# 02_MCU.net
KiCad netlist of a schematic drawn in Altium Designer
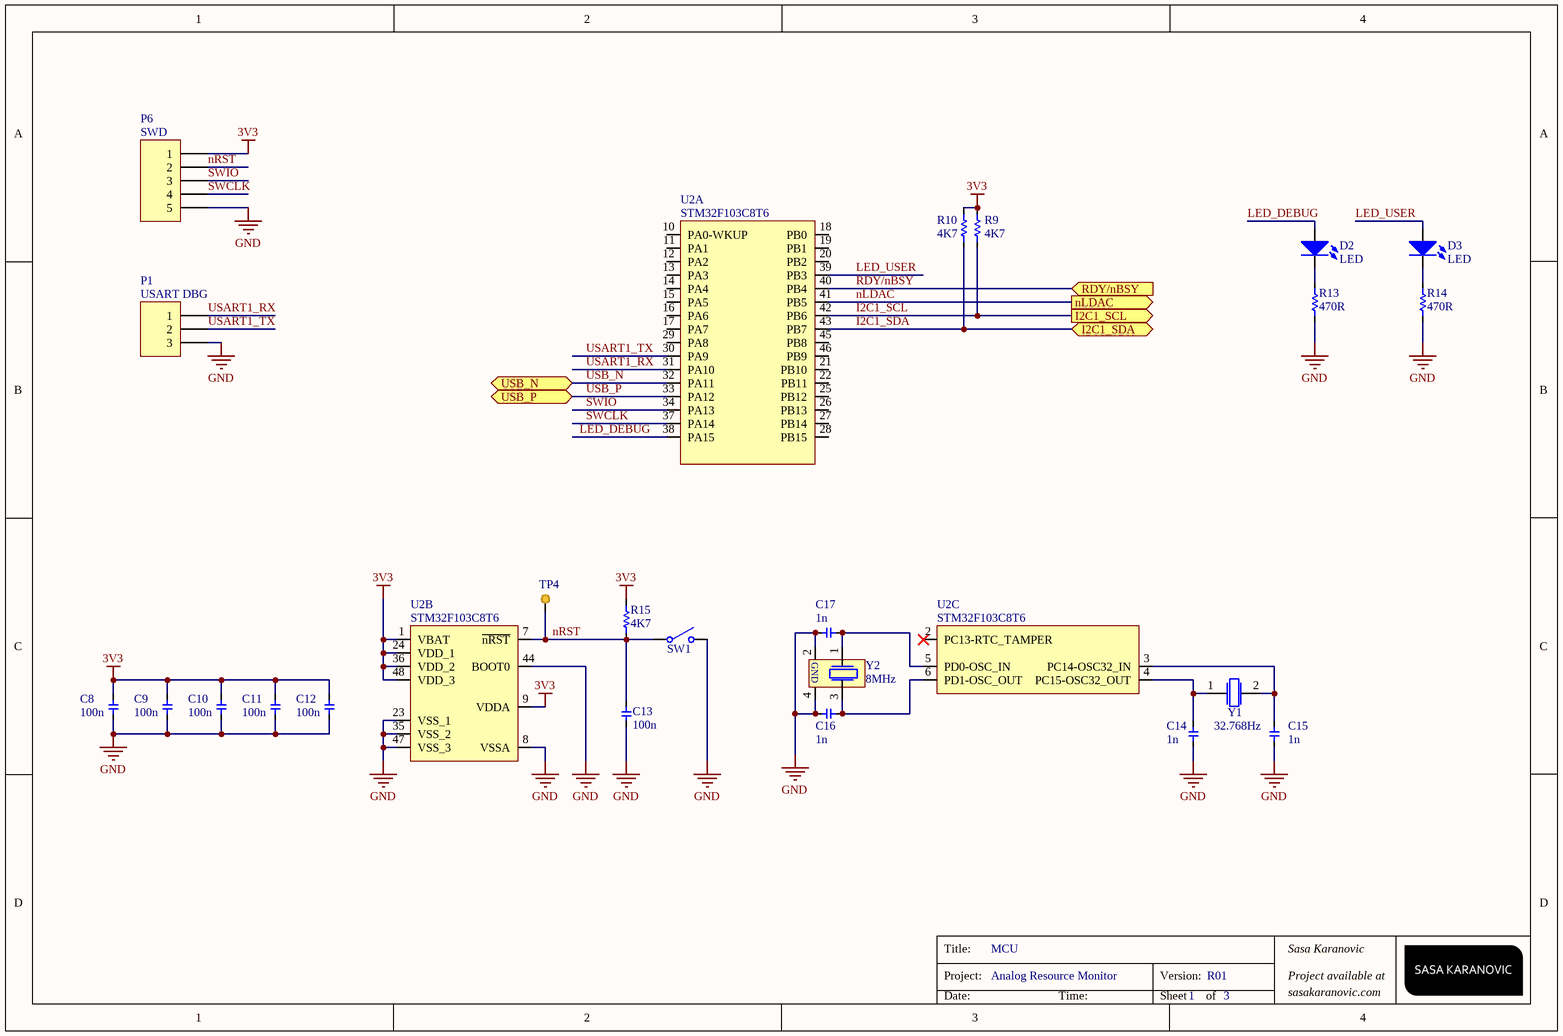
[diagram p0: 02_MCU.SchDoc]

(export (version "E")
  (design (tool "Eeschema 10.0.6"))
  (components
    (comp (ref "C8")
      (value "100n")
      (footprint "Moji Footprintovi:0603 - CAP")
      (description "Capacitor")
      (fields
        (field (name "MANUFACTURER") "AVX Corporation")
        (field (name "MANUFACTURER PART NUMBER") "06035C104KAT2A")
      )
      (libsource (lib "Moji Schematici") (part "Cap"))
    )
    (comp (ref "C9")
      (value "100n")
      (footprint "Moji Footprintovi:0603 - CAP")
      (description "Capacitor")
      (fields
        (field (name "MANUFACTURER") "AVX Corporation")
        (field (name "MANUFACTURER PART NUMBER") "06035C104KAT2A")
      )
      (libsource (lib "Moji Schematici") (part "Cap"))
    )
    (comp (ref "C10")
      (value "100n")
      (footprint "Moji Footprintovi:0603 - CAP")
      (description "Capacitor")
      (fields
        (field (name "MANUFACTURER") "AVX Corporation")
        (field (name "MANUFACTURER PART NUMBER") "06035C104KAT2A")
      )
      (libsource (lib "Moji Schematici") (part "Cap"))
    )
    (comp (ref "C11")
      (value "100n")
      (footprint "Moji Footprintovi:0603 - CAP")
      (description "Capacitor")
      (fields
        (field (name "MANUFACTURER") "AVX Corporation")
        (field (name "MANUFACTURER PART NUMBER") "06035C104KAT2A")
      )
      (libsource (lib "Moji Schematici") (part "Cap"))
    )
    (comp (ref "C12")
      (value "100n")
      (footprint "Moji Footprintovi:0603 - CAP")
      (description "Capacitor")
      (fields
        (field (name "MANUFACTURER") "AVX Corporation")
        (field (name "MANUFACTURER PART NUMBER") "06035C104KAT2A")
      )
      (libsource (lib "Moji Schematici") (part "Cap"))
    )
    (comp (ref "C13")
      (value "100n")
      (footprint "Moji Footprintovi:0603 - CAP")
      (description "Capacitor")
      (fields
        (field (name "MANUFACTURER") "AVX Corporation")
        (field (name "MANUFACTURER PART NUMBER") "06035C104KAT2A")
      )
      (libsource (lib "Moji Schematici") (part "Cap"))
    )
    (comp (ref "C14")
      (value "1n")
      (footprint "Moji Footprintovi:0603 - CAP")
      (description "Capacitor")
      (fields (field (name "Comment") "Cap"))
      (libsource (lib "Moji Schematici") (part "Cap"))
    )
    (comp (ref "C15")
      (value "1n")
      (footprint "Moji Footprintovi:0603 - CAP")
      (description "Capacitor")
      (fields (field (name "Comment") "Cap"))
      (libsource (lib "Moji Schematici") (part "Cap"))
    )
    (comp (ref "C16")
      (value "1n")
      (footprint "Moji Footprintovi:0603 - CAP")
      (description "Capacitor")
      (fields (field (name "Comment") "Cap"))
      (libsource (lib "Moji Schematici") (part "Cap"))
    )
    (comp (ref "C17")
      (value "1n")
      (footprint "Moji Footprintovi:0603 - CAP")
      (description "Capacitor")
      (fields (field (name "Comment") "Cap"))
      (libsource (lib "Moji Schematici") (part "Cap"))
    )
    (comp (ref "D2")
      (value "LED")
      (footprint "Moji Footprintovi:0603 Diode")
      (description "Typical RED GaAs LED")
      (libsource (lib "Moji Schematici") (part "LED"))
    )
    (comp (ref "D3")
      (value "LED")
      (footprint "Moji Footprintovi:0603 Diode")
      (description "Typical RED GaAs LED")
      (libsource (lib "Moji Schematici") (part "LED"))
    )
    (comp (ref "P1")
      (value "USART DBG")
      (footprint "Moji Footprintovi:Header 3x1 SMD")
      (description "Header, 3-Pin")
      (libsource (lib "Moji Schematici") (part "Header 3"))
    )
    (comp (ref "P6")
      (value "SWD")
      (footprint "Moji Footprintovi:Header 5x1 SMD")
      (description "Header, 5-Pin")
      (libsource (lib "Moji Schematici") (part "Header 5"))
    )
    (comp (ref "R9")
      (value "4K7")
      (footprint "Moji Footprintovi:0603")
      (description "Resistor")
      (fields
        (field (name "MANUFACTURER") "Yageo")
        (field (name "MANUFACTURER PART NUMBER") "RC0603JR-070RL")
      )
      (libsource (lib "Moji Schematici") (part "Res"))
    )
    (comp (ref "R10")
      (value "4K7")
      (footprint "Moji Footprintovi:0603")
      (description "Resistor")
      (fields
        (field (name "MANUFACTURER") "Yageo")
        (field (name "MANUFACTURER PART NUMBER") "RC0603JR-070RL")
      )
      (libsource (lib "Moji Schematici") (part "Res"))
    )
    (comp (ref "R13")
      (value "470R")
      (footprint "Moji Footprintovi:0603")
      (description "Resistor")
      (fields
        (field (name "MANUFACTURER") "Yageo")
        (field (name "MANUFACTURER PART NUMBER") "RC0603FR-07470RL")
      )
      (libsource (lib "Moji Schematici") (part "Res"))
    )
    (comp (ref "R14")
      (value "470R")
      (footprint "Moji Footprintovi:0603")
      (description "Resistor")
      (fields
        (field (name "MANUFACTURER") "Yageo")
        (field (name "MANUFACTURER PART NUMBER") "RC0603FR-07470RL")
      )
      (libsource (lib "Moji Schematici") (part "Res"))
    )
    (comp (ref "R15")
      (value "4K7")
      (footprint "Moji Footprintovi:0603")
      (description "Resistor")
      (fields
        (field (name "MANUFACTURER") "Yageo")
        (field (name "MANUFACTURER PART NUMBER") "RC0603JR-070RL")
      )
      (libsource (lib "Moji Schematici") (part "Res"))
    )
    (comp (ref "SW1")
      (value "Switch")
      (footprint "Moji Footprintovi:EVQ-5PN04K")
      (description "SWITCH TACTILE SPST-NO 0.05A 12V")
      (fields
        (field (name "DISTRIBUTOR PART NUMBER") "P13595SCT-ND")
        (field (name "MANUFACTURER") "Panasonic Electronic Components")
      )
      (libsource (lib "Moji Schematici") (part "EVQ-5PN04K"))
    )
    (comp (ref "TP4")
      (value "Test Point 0.6mm")
      (footprint "Moji Footprintovi:TP_SMD_1mm")
      (libsource (lib "Moji Schematici") (part "TP"))
    )
    (comp (ref "U2")
      (value "STM32F103C8T6")
      (footprint "Moji Footprintovi:LQFP48_7x7mm")
      (description "IC MCU 32BIT 64KB FLASH 48LQFP")
      (fields
        (field (name "DISTRIBUTOR PART NUMBER") "497-6063-ND")
        (field (name "MANUFACTURER") "STMicroelectronics")
      )
      (libsource (lib "Moji Schematici") (part "STM32F103C8T6"))
    )
    (comp (ref "Y1")
      (value "32.768Hz")
      (footprint "Moji Footprintovi:ABS07-120")
      (description "CRYSTAL 32.7680KHZ 6PF SMD")
      (fields
        (field (name "DISTRIBUTOR PART NUMBER") "535-11937-1-ND")
        (field (name "MANUFACTURER") "Abracon LLC")
      )
      (libsource (lib "Moji Schematici") (part "ABS07-120-32.768KHZ-T"))
    )
    (comp (ref "Y2")
      (value "8MHz")
      (footprint "Moji Footprintovi:ABM8G")
      (description "CRYSTAL 16.0000MHZ 10PF SMD")
      (fields
        (field (name "DISTRIBUTOR PART NUMBER") "535-10907-1-ND")
        (field (name "MANUFACTURER") "Abracon LLC")
      )
      (libsource (lib "Moji Schematici") (part "ABM8G"))
    )
  )
  (nets
    (net (code "1") (name "/I2C1_SCL") (class "Default")
      (node (ref "R9") (pin "2") (pinfunction "2_2") (pintype "passive"))
      (node (ref "U2") (pin "42") (pinfunction "PB6_42") (pintype "passive"))
    )
    (net (code "2") (name "/I2C1_SDA") (class "Default")
      (node (ref "R10") (pin "2") (pinfunction "2_2") (pintype "passive"))
      (node (ref "U2") (pin "43") (pinfunction "PB7_43") (pintype "passive"))
    )
    (net (code "3") (name "/LED_DEBUG") (class "Default")
      (node (ref "D2") (pin "A") (pinfunction "A_A") (pintype "passive"))
      (node (ref "U2") (pin "38") (pinfunction "PA15_38") (pintype "passive"))
    )
    (net (code "4") (name "/LED_USER") (class "Default")
      (node (ref "D3") (pin "A") (pinfunction "A_A") (pintype "passive"))
      (node (ref "U2") (pin "39") (pinfunction "PB3_39") (pintype "passive"))
    )
    (net (code "5") (name "/RDY{slash}nBSY") (class "Default")
      (node (ref "U2") (pin "40") (pinfunction "PB4_40") (pintype "passive"))
    )
    (net (code "6") (name "/SWCLK") (class "Default")
      (node (ref "P6") (pin "4") (pinfunction "4_4") (pintype "passive"))
      (node (ref "U2") (pin "37") (pinfunction "PA14_37") (pintype "passive"))
    )
    (net (code "7") (name "/SWIO") (class "Default")
      (node (ref "P6") (pin "3") (pinfunction "3_3") (pintype "passive"))
      (node (ref "U2") (pin "34") (pinfunction "PA13_34") (pintype "passive"))
    )
    (net (code "8") (name "/USART1_RX") (class "Default")
      (node (ref "P1") (pin "1") (pinfunction "1_1") (pintype "passive"))
      (node (ref "U2") (pin "31") (pinfunction "PA10_31") (pintype "passive"))
    )
    (net (code "9") (name "/USART1_TX") (class "Default")
      (node (ref "P1") (pin "2") (pinfunction "2_2") (pintype "passive"))
      (node (ref "U2") (pin "30") (pinfunction "PA9_30") (pintype "passive"))
    )
    (net (code "10") (name "/USB_N") (class "Default")
      (node (ref "U2") (pin "32") (pinfunction "PA11_32") (pintype "passive"))
    )
    (net (code "11") (name "/USB_P") (class "Default")
      (node (ref "U2") (pin "33") (pinfunction "PA12_33") (pintype "passive"))
    )
    (net (code "12") (name "/nLDAC") (class "Default")
      (node (ref "U2") (pin "41") (pinfunction "PB5_41") (pintype "passive"))
    )
    (net (code "13") (name "/nRST") (class "Default")
      (node (ref "C13") (pin "2") (pinfunction "2_2") (pintype "passive"))
      (node (ref "P6") (pin "2") (pinfunction "2_2") (pintype "passive"))
      (node (ref "R15") (pin "2") (pinfunction "2_2") (pintype "passive"))
      (node (ref "SW1") (pin "1") (pinfunction "COMMON1_1") (pintype "passive"))
      (node (ref "TP4") (pin "1") (pinfunction "1_1") (pintype "passive"))
      (node (ref "U2") (pin "7") (pinfunction "~{nRST}_7") (pintype "passive"))
    )
    (net (code "14") (name "3V3") (class "Default")
      (node (ref "C10") (pin "2") (pinfunction "2_2") (pintype "passive"))
      (node (ref "C11") (pin "2") (pinfunction "2_2") (pintype "passive"))
      (node (ref "C12") (pin "2") (pinfunction "2_2") (pintype "passive"))
      (node (ref "C8") (pin "2") (pinfunction "2_2") (pintype "passive"))
      (node (ref "C9") (pin "2") (pinfunction "2_2") (pintype "passive"))
      (node (ref "P6") (pin "1") (pinfunction "1_1") (pintype "passive"))
      (node (ref "R10") (pin "1") (pinfunction "1_1") (pintype "passive"))
      (node (ref "R15") (pin "1") (pinfunction "1_1") (pintype "passive"))
      (node (ref "R9") (pin "1") (pinfunction "1_1") (pintype "passive"))
      (node (ref "U2") (pin "1") (pinfunction "VBAT_1") (pintype "passive"))
      (node (ref "U2") (pin "24") (pinfunction "VDD_1_24") (pintype "passive"))
      (node (ref "U2") (pin "36") (pinfunction "VDD_2_36") (pintype "passive"))
      (node (ref "U2") (pin "48") (pinfunction "VDD_3_48") (pintype "passive"))
      (node (ref "U2") (pin "9") (pinfunction "VDDA_9") (pintype "passive"))
    )
    (net (code "15") (name "GND") (class "Default")
      (node (ref "C10") (pin "1") (pinfunction "1_1") (pintype "passive"))
      (node (ref "C11") (pin "1") (pinfunction "1_1") (pintype "passive"))
      (node (ref "C12") (pin "1") (pinfunction "1_1") (pintype "passive"))
      (node (ref "C13") (pin "1") (pinfunction "1_1") (pintype "passive"))
      (node (ref "C14") (pin "1") (pinfunction "1_1") (pintype "passive"))
      (node (ref "C15") (pin "1") (pinfunction "1_1") (pintype "passive"))
      (node (ref "C16") (pin "2") (pinfunction "2_2") (pintype "passive"))
      (node (ref "C17") (pin "2") (pinfunction "2_2") (pintype "passive"))
      (node (ref "C8") (pin "1") (pinfunction "1_1") (pintype "passive"))
      (node (ref "C9") (pin "1") (pinfunction "1_1") (pintype "passive"))
      (node (ref "P1") (pin "3") (pinfunction "3_3") (pintype "passive"))
      (node (ref "P6") (pin "5") (pinfunction "5_5") (pintype "passive"))
      (node (ref "R13") (pin "2") (pinfunction "2_2") (pintype "passive"))
      (node (ref "R14") (pin "2") (pinfunction "2_2") (pintype "passive"))
      (node (ref "SW1") (pin "2") (pinfunction "COMMON2_2") (pintype "passive"))
      (node (ref "U2") (pin "23") (pinfunction "VSS_1_23") (pintype "passive"))
      (node (ref "U2") (pin "35") (pinfunction "VSS_2_35") (pintype "passive"))
      (node (ref "U2") (pin "44") (pinfunction "BOOT0_44") (pintype "passive"))
      (node (ref "U2") (pin "47") (pinfunction "VSS_3_47") (pintype "passive"))
      (node (ref "U2") (pin "8") (pinfunction "VSSA_8") (pintype "passive"))
      (node (ref "Y2") (pin "2") (pinfunction "OSC2_2") (pintype "passive"))
      (node (ref "Y2") (pin "4") (pinfunction "OSC4_4") (pintype "passive"))
    )
    (net (code "16") (name "Net-(D2-PadK)") (class "Default")
      (node (ref "D2") (pin "K") (pinfunction "K_K") (pintype "passive"))
      (node (ref "R13") (pin "1") (pinfunction "1_1") (pintype "passive"))
    )
    (net (code "17") (name "Net-(D3-PadK)") (class "Default")
      (node (ref "D3") (pin "K") (pinfunction "K_K") (pintype "passive"))
      (node (ref "R14") (pin "1") (pinfunction "1_1") (pintype "passive"))
    )
    (net (code "18") (name "Net-(U2C-PC14-OSC32_IN)") (class "Default")
      (node (ref "C15") (pin "2") (pinfunction "2_2") (pintype "passive"))
      (node (ref "U2") (pin "3") (pinfunction "PC14-OSC32_IN_3") (pintype "passive"))
      (node (ref "Y1") (pin "2") (pinfunction "OSC2_2") (pintype "passive"))
    )
    (net (code "19") (name "Net-(U2C-PC15-OSC32_OUT)") (class "Default")
      (node (ref "C14") (pin "2") (pinfunction "2_2") (pintype "passive"))
      (node (ref "U2") (pin "4") (pinfunction "PC15-OSC32_OUT_4") (pintype "passive"))
      (node (ref "Y1") (pin "1") (pinfunction "OSC1_1") (pintype "passive"))
    )
    (net (code "20") (name "Net-(U2C-PD0-OSC_IN)") (class "Default")
      (node (ref "C17") (pin "1") (pinfunction "1_1") (pintype "passive"))
      (node (ref "U2") (pin "5") (pinfunction "PD0-OSC_IN_5") (pintype "passive"))
      (node (ref "Y2") (pin "1") (pinfunction "OSC1_1") (pintype "passive"))
    )
    (net (code "21") (name "Net-(U2C-PD1-OSC_OUT)") (class "Default")
      (node (ref "C16") (pin "1") (pinfunction "1_1") (pintype "passive"))
      (node (ref "U2") (pin "6") (pinfunction "PD1-OSC_OUT_6") (pintype "passive"))
      (node (ref "Y2") (pin "3") (pinfunction "OSC3_3") (pintype "passive"))
    )
    (net (code "22") (name "unconnected-(U2A-PA0-WKUP-Pad10)") (class "Default")
      (node (ref "U2") (pin "10") (pinfunction "PA0-WKUP_10") (pintype "passive"))
    )
    (net (code "23") (name "unconnected-(U2A-PA1-Pad11)") (class "Default")
      (node (ref "U2") (pin "11") (pinfunction "PA1_11") (pintype "passive"))
    )
    (net (code "24") (name "unconnected-(U2A-PA2-Pad12)") (class "Default")
      (node (ref "U2") (pin "12") (pinfunction "PA2_12") (pintype "passive"))
    )
    (net (code "25") (name "unconnected-(U2A-PA3-Pad13)") (class "Default")
      (node (ref "U2") (pin "13") (pinfunction "PA3_13") (pintype "passive"))
    )
    (net (code "26") (name "unconnected-(U2A-PA4-Pad14)") (class "Default")
      (node (ref "U2") (pin "14") (pinfunction "PA4_14") (pintype "passive"))
    )
    (net (code "27") (name "unconnected-(U2A-PA5-Pad15)") (class "Default")
      (node (ref "U2") (pin "15") (pinfunction "PA5_15") (pintype "passive"))
    )
    (net (code "28") (name "unconnected-(U2A-PA6-Pad16)") (class "Default")
      (node (ref "U2") (pin "16") (pinfunction "PA6_16") (pintype "passive"))
    )
    (net (code "29") (name "unconnected-(U2A-PA7-Pad17)") (class "Default")
      (node (ref "U2") (pin "17") (pinfunction "PA7_17") (pintype "passive"))
    )
    (net (code "30") (name "unconnected-(U2A-PA8-Pad29)") (class "Default")
      (node (ref "U2") (pin "29") (pinfunction "PA8_29") (pintype "passive"))
    )
    (net (code "31") (name "unconnected-(U2A-PB0-Pad18)") (class "Default")
      (node (ref "U2") (pin "18") (pinfunction "PB0_18") (pintype "passive"))
    )
    (net (code "32") (name "unconnected-(U2A-PB1-Pad19)") (class "Default")
      (node (ref "U2") (pin "19") (pinfunction "PB1_19") (pintype "passive"))
    )
    (net (code "33") (name "unconnected-(U2A-PB2-Pad20)") (class "Default")
      (node (ref "U2") (pin "20") (pinfunction "PB2_20") (pintype "passive"))
    )
    (net (code "34") (name "unconnected-(U2A-PB8-Pad45)") (class "Default")
      (node (ref "U2") (pin "45") (pinfunction "PB8_45") (pintype "passive"))
    )
    (net (code "35") (name "unconnected-(U2A-PB9-Pad46)") (class "Default")
      (node (ref "U2") (pin "46") (pinfunction "PB9_46") (pintype "passive"))
    )
    (net (code "36") (name "unconnected-(U2A-PB10-Pad21)") (class "Default")
      (node (ref "U2") (pin "21") (pinfunction "PB10_21") (pintype "passive"))
    )
    (net (code "37") (name "unconnected-(U2A-PB11-Pad22)") (class "Default")
      (node (ref "U2") (pin "22") (pinfunction "PB11_22") (pintype "passive"))
    )
    (net (code "38") (name "unconnected-(U2A-PB12-Pad25)") (class "Default")
      (node (ref "U2") (pin "25") (pinfunction "PB12_25") (pintype "passive"))
    )
    (net (code "39") (name "unconnected-(U2A-PB13-Pad26)") (class "Default")
      (node (ref "U2") (pin "26") (pinfunction "PB13_26") (pintype "passive"))
    )
    (net (code "40") (name "unconnected-(U2A-PB14-Pad27)") (class "Default")
      (node (ref "U2") (pin "27") (pinfunction "PB14_27") (pintype "passive"))
    )
    (net (code "41") (name "unconnected-(U2A-PB15-Pad28)") (class "Default")
      (node (ref "U2") (pin "28") (pinfunction "PB15_28") (pintype "passive"))
    )
    (net (code "42") (name "unconnected-(U2C-PC13-RTC_TAMPER-Pad2)") (class "Default")
      (node (ref "U2") (pin "2") (pinfunction "PC13-RTC_TAMPER_2") (pintype "passive+no_connect"))
    )
  )
)
